# 1_Power_supply.net
KiCad netlist of a schematic drawn in Altium Designer
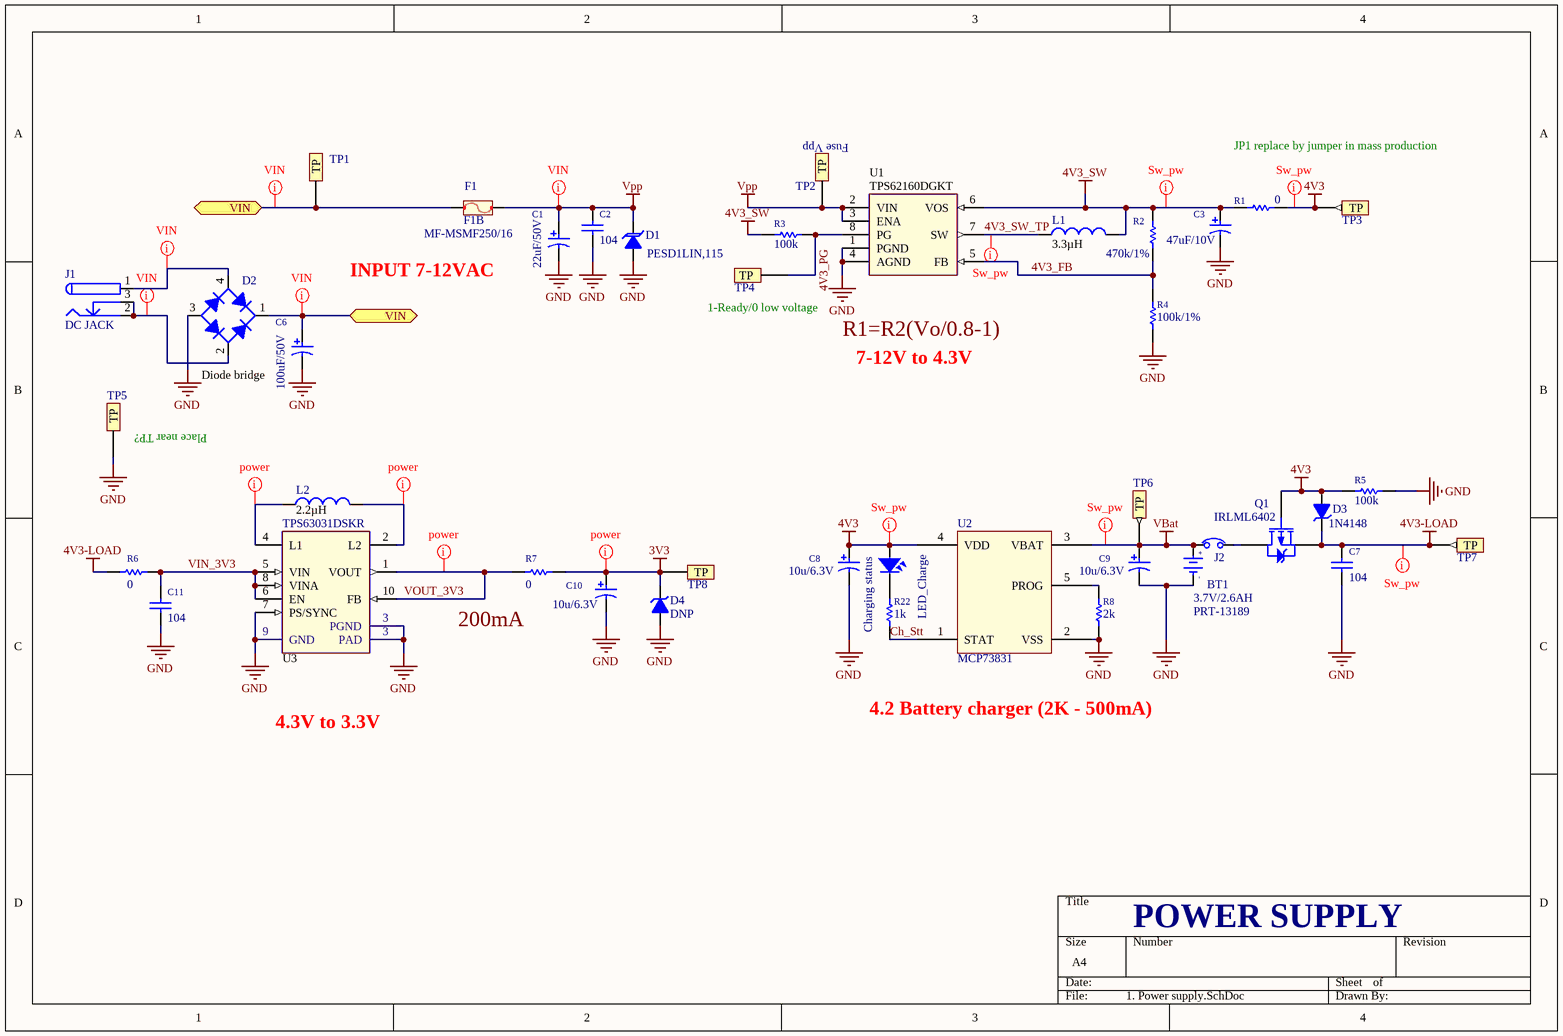
[diagram p0: 1. Power supply.SchDoc]

(export (version "E")
  (design (tool "Eeschema 10.0.6"))
  (components
    (comp (ref "BT1")
      (value "3.7V/2.6AH")
      (footprint "Batterry Cell")
      (description "BATTERY LITHIUM 3.7V 2.6AH")
      (fields
        (field (name "ALTIUM_VALUE") "PRT-13189")
        (field (name "MANUFACTURER") "SparkFun Electronics")
        (field (name "PART") "PRT-13189")
      )
      (libsource (lib "LIB_MISCELLANEOUS") (part "PIN 3V"))
    )
    (comp (ref "C1")
      (value "22uF/50V")
      (footprint "CAP_SMD_6_3MM_N")
      (description "CAP ALUM 22UF 20% 50V SMD")
      (fields (field (name "MANUFACTURER") "Panasonic Electronic Components") (field (name "VOLTAGE") "50V"))
      (libsource (lib "My_Integrated_Library") (part "Cap_Pol"))
    )
    (comp (ref "C2")
      (value "104")
      (footprint "sm-0603-c")
      (description "CAP CER 10000PF 16V 0603")
      (fields (field (name "MANUFACTURER") "Taiyo Yuden") (field (name "PART") "EMK107SD103JA-T"))
      (libsource (lib "My_Integrated_Library") (part "Capacitor"))
    )
    (comp (ref "C3")
      (value "47uF/10V")
      (footprint "Cap SMD Tant - 470u")
      (description "47uF/10V ±10% SMD Tantalum Capacitor")
      (fields (field (name "MANUFACTURER") "AVX") (field (name "VOLTAGE") "10V"))
      (libsource (lib "My_Integrated_Library") (part "Cap_Pol"))
    )
    (comp (ref "C6")
      (value "100uF/50V")
      (footprint "CAP SMD ALUMINUM G.CAOVANHUONG")
      (description "CAP ALUM 22UF 20% 50V SMD")
      (fields (field (name "MANUFACTURER") "Panasonic Electronic Components") (field (name "VOLTAGE") "50V"))
      (libsource (lib "My_Integrated_Library") (part "Cap_Pol"))
    )
    (comp (ref "C7")
      (value "104")
      (footprint "sm-0603-c")
      (description "CAP CER 10000PF 16V 0603")
      (fields (field (name "MANUFACTURER") "Taiyo Yuden") (field (name "PART") "EMK107SD103JA-T"))
      (libsource (lib "My_Integrated_Library") (part "Capacitor"))
    )
    (comp (ref "C8")
      (value "10u/6.3V")
      (footprint "Cap SMD Tant 10u")
      (description "CAP CER 10UF 6.3V X5R 1206")
      (fields (field (name "MANUFACTURER") "Samsung Electro-Mechanics") (field (name "VOLTAGE") "6.3V"))
      (libsource (lib "My_Integrated_Library") (part "Cap_Pol"))
    )
    (comp (ref "C9")
      (value "10u/6.3V")
      (footprint "Cap SMD Tant 10u")
      (description "CAP CER 10UF 6.3V X5R 1206")
      (fields (field (name "MANUFACTURER") "Samsung Electro-Mechanics") (field (name "VOLTAGE") "6.3V"))
      (libsource (lib "My_Integrated_Library") (part "Cap_Pol"))
    )
    (comp (ref "C10")
      (value "10u/6.3V")
      (footprint "Cap SMD Tant 10u")
      (description "CAP CER 10UF 6.3V X5R 1206")
      (fields (field (name "MANUFACTURER") "Samsung Electro-Mechanics") (field (name "VOLTAGE") "6.3V"))
      (libsource (lib "My_Integrated_Library") (part "Cap_Pol"))
    )
    (comp (ref "C11")
      (value "104")
      (footprint "sm-0603-c")
      (description "CAP CER 10000PF 16V 0603")
      (fields (field (name "MANUFACTURER") "Taiyo Yuden") (field (name "PART") "EMK107SD103JA-T"))
      (libsource (lib "My_Integrated_Library") (part "Capacitor"))
    )
    (comp (ref "D1")
      (value "PESD1LIN,115")
      (footprint "DIODE_SMB")
      (description "TVS DIODE 15V/24V 44V/70V SOD323")
      (fields (field (name "MANUFACTURER") "Nexperia USA Inc.") (field (name "POWER") "160W"))
      (libsource (lib "LIB_MISCELLANEOUS") (part "Diode TVS"))
    )
    (comp (ref "D2")
      (value "Diode bridge")
      (footprint "DB-38R")
      (description "Rectifier Bridge")
      (fields (field (name "PART") "Diode_Bridge") (field (name "Comment") "Diode Bridge"))
      (libsource (lib "My_Integrated_Library") (part "Diode_Bridge"))
    )
    (comp (ref "D3")
      (value "1N4148")
      (footprint "DIODE-SOD80")
      (description "Zener Diode")
      (fields (field (name "MANUFACTURER") "Unknow"))
      (libsource (lib "LIB_MISCELLANEOUS") (part "Diode Zener"))
    )
    (comp (ref "D4")
      (value "DNP")
      (footprint "DIODE-SOD80")
      (description "Zener Diode")
      (fields (field (name "MANUFACTURER") "Unknow"))
      (libsource (lib "LIB_MISCELLANEOUS") (part "Diode Zener"))
    )
    (comp (ref "F1")
      (value "F1B")
      (footprint "SMD-PTC")
      (description "2.5A/16V SMD-1812 PTC Resettable Fuses")
      (fields
        (field (name "ALTIUM_VALUE") "MF-MSMF250/16")
        (field (name "MANUFACTURER") "Bourns Inc.")
        (field (name "PART") "MF-MSMF250/16")
      )
      (libsource (lib "LIB_MISCELLANEOUS") (part "Fuse"))
    )
    (comp (ref "J1")
      (value "DC JACK")
      (footprint "DC JACK.CAOVANHUONG")
      (description "Low Voltage Power Supply Connector")
      (fields (field (name "PUBLISHER") "Altium Limited"))
      (libsource (lib "caovanhuong") (part "DC JACK"))
    )
    (comp (ref "J2")
      (value "jumper selector")
      (footprint "CON.HDR1X2")
      (libsource (lib "My_Integrated_Library") (part "jumper selector"))
    )
    (comp (ref "L1")
      (value "3.3µH")
      (footprint "Inductor 2")
      (description "FIXED IND 3.3UH 3.2A 30.2 MOHM")
      (fields (field (name "MANUFACTURER") "Bourns Inc."))
      (libsource (lib "My_Integrated_Library") (part "Inductor"))
    )
    (comp (ref "L2")
      (value "2.2µH")
      (footprint "INDUCTOR 4")
      (description "FIXED IND 2.2UH 2.9A 42 MOHM SMD")
      (fields (field (name "MANUFACTURER") "Taiyo Yuden"))
      (libsource (lib "My_Integrated_Library") (part "Inductor"))
    )
    (comp (ref "LED_Charge")
      (value "Charging status")
      (footprint "LED0603")
      (description "LED Single colour Green and Red")
      (fields (field (name "MANUFACTURER") "Unknow"))
      (libsource (lib "LIB_MISCELLANEOUS") (part "LED"))
    )
    (comp (ref "Q1")
      (value "IRLML6402")
      (footprint "SOT23-3.CAOVANHUONG")
      (description "P-Channel MOSFET, ID =3.7A @ TA = 25°C, VGS @ -4.5V")
      (fields (field (name "PUBLISHER") "Altium Limited"))
      (libsource (lib "caovanhuong") (part "IRLML6402"))
    )
    (comp (ref "R1")
      (value "0")
      (footprint "R2012-0805")
      (description "RES SMD 0 OHM JUMPER 1/10W 0805")
      (fields (field (name "MANUFACTURER") "Panasonic Electronic Components") (field (name "POWER") "1/10W"))
      (libsource (lib "My_Integrated_Library") (part "Resistor"))
    )
    (comp (ref "R2")
      (value "470k/1%")
      (footprint "SM-0603-R")
      (description "RES SMD 470K OHM 1% 1/10W 0603")
      (fields (field (name "MANUFACTURER") "Panasonic Electronic Components") (field (name "PART") "470k"))
      (libsource (lib "My_Integrated_Library") (part "Resistor"))
    )
    (comp (ref "R3")
      (value "100k")
      (footprint "SM-0603-R")
      (description "RES SMD 100K OHM 5% 1/10W 0603")
      (fields (field (name "MANUFACTURER") "Panasonic Electronic Components") (field (name "POWER") "1/10W"))
      (libsource (lib "My_Integrated_Library") (part "Resistor"))
    )
    (comp (ref "R4")
      (value "100k/1%")
      (footprint "SM-0603-R")
      (description "RES SMD 100K OHM 1% 1/10W 0603")
      (fields (field (name "MANUFACTURER") "Panasonic Electronic Components") (field (name "PART") "100k"))
      (libsource (lib "My_Integrated_Library") (part "Resistor"))
    )
    (comp (ref "R5")
      (value "100k")
      (footprint "SM-0603-R")
      (description "RES SMD 100K OHM 5% 1/10W 0603")
      (fields (field (name "MANUFACTURER") "Panasonic Electronic Components") (field (name "POWER") "1/10W"))
      (libsource (lib "My_Integrated_Library") (part "Resistor"))
    )
    (comp (ref "R6")
      (value "0")
      (footprint "R2012-0805")
      (description "RES SMD 0 OHM JUMPER 1/10W 0805")
      (fields (field (name "MANUFACTURER") "Panasonic Electronic Components") (field (name "POWER") "1/10W"))
      (libsource (lib "My_Integrated_Library") (part "Resistor"))
    )
    (comp (ref "R7")
      (value "0")
      (footprint "R2012-0805")
      (description "RES SMD 0 OHM JUMPER 1/10W 0805")
      (fields (field (name "MANUFACTURER") "Panasonic Electronic Components") (field (name "POWER") "1/10W"))
      (libsource (lib "My_Integrated_Library") (part "Resistor"))
    )
    (comp (ref "R8")
      (value "2k")
      (footprint "SM-0603-R")
      (description "RES SMD 100K OHM 5% 1/10W 0603")
      (fields (field (name "MANUFACTURER") "Panasonic Electronic Components") (field (name "PART") "100k"))
      (libsource (lib "My_Integrated_Library") (part "Resistor"))
    )
    (comp (ref "R22")
      (value "1k")
      (footprint "SM-0603-R")
      (description "RES SMD 1K OHM 5% 1/10W 0603")
      (fields (field (name "MANUFACTURER") "Panasonic Electronic Components") (field (name "POWER") "1/10W"))
      (libsource (lib "My_Integrated_Library") (part "Resistor"))
    )
    (comp (ref "TP1")
      (value "Vin")
      (footprint "TP")
      (description "Test Point")
      (libsource (lib "My_Integrated_Library") (part "Test Point"))
    )
    (comp (ref "TP2")
      (value "VIN")
      (footprint "TP")
      (description "Test Point")
      (libsource (lib "My_Integrated_Library") (part "Test Point"))
    )
    (comp (ref "TP3")
      (value "4V3")
      (footprint "TP")
      (description "Test Point")
      (libsource (lib "") (part "Test Point_1"))
    )
    (comp (ref "TP4")
      (value "4V3_PG")
      (footprint "TP")
      (description "Test Point")
      (libsource (lib "") (part "Test Point_3"))
    )
    (comp (ref "TP5")
      (value "GND")
      (footprint "TP")
      (description "Test Point")
      (libsource (lib "My_Integrated_Library") (part "Test Point"))
    )
    (comp (ref "TP6")
      (value "4V3")
      (footprint "TP")
      (description "Test Point")
      (libsource (lib "My_Integrated_Library") (part "Test Point"))
    )
    (comp (ref "TP7")
      (value "4V3")
      (footprint "TP")
      (description "Test Point")
      (libsource (lib "") (part "Test Point_1"))
    )
    (comp (ref "TP8")
      (value "TP")
      (footprint "TP")
      (description "Test Point")
      (libsource (lib "") (part "Test Point_2"))
    )
    (comp (ref "U1")
      (value "TPS62160DGKT")
      (footprint "SSOP8.S-PDSO-G8")
      (description "IC REG BUCK ADJ 1A SYNC 8VSSOP")
      (fields (field (name "MANUFACTURER") "Texas Instruments"))
      (libsource (lib "My_Integrated_Library") (part "TPS62160"))
    )
    (comp (ref "U2")
      (value "MCP73831")
      (footprint "SOT23-5.CAOVANHUONG")
      (description "Miniature Single Cell, Fully Integrated Li-Ion,  Li-Polymer Charge Management ControllerController")
      (fields (field (name "MANUFACTURER") "Microchip"))
      (libsource (lib "caovanhuong") (part "MCP73831"))
    )
    (comp (ref "U3")
      (value "TPS63031DSKR")
      (footprint "WSON10")
      (description "IC REG BUCK BST 3.3V 0.9A 10SON")
      (fields (field (name "MANUFACTURER") "Texas Instruments"))
      (libsource (lib "My_Integrated_Library") (part "TPS63031"))
    )
  )
  (nets
    (net (code "1") (name "/4V3_FB") (class "Default")
      (node (ref "R2") (pin "2") (pinfunction "2_2") (pintype "passive"))
      (node (ref "R4") (pin "1") (pinfunction "1_1") (pintype "passive"))
      (node (ref "U1") (pin "5") (pinfunction "FB_5") (pintype "input"))
    )
    (net (code "2") (name "/4V3_PG") (class "Default")
      (node (ref "R3") (pin "1") (pinfunction "1_1") (pintype "passive"))
      (node (ref "TP4") (pin "1") (pinfunction "TP_1") (pintype "passive"))
      (node (ref "U1") (pin "8") (pinfunction "PG_8") (pintype "open_collector"))
    )
    (net (code "3") (name "/4V3_SW_TP") (class "Default")
      (node (ref "L1") (pin "1") (pinfunction "1_1") (pintype "passive"))
      (node (ref "U1") (pin "7") (pinfunction "SW_7") (pintype "output"))
    )
    (net (code "4") (name "/Ch_Stt") (class "Default")
      (node (ref "R22") (pin "1") (pinfunction "1_1") (pintype "passive"))
      (node (ref "U2") (pin "1") (pinfunction "STAT_1") (pintype "passive"))
    )
    (net (code "5") (name "/VIN") (class "Default")
      (node (ref "C6") (pin "1") (pinfunction "1_1") (pintype "passive"))
      (node (ref "D2") (pin "1") (pinfunction "K_1") (pintype "passive"))
      (node (ref "F1") (pin "1") (pinfunction "1_1") (pintype "passive"))
      (node (ref "TP1") (pin "1") (pinfunction "TP_1") (pintype "passive"))
    )
    (net (code "6") (name "/VIN_3V3") (class "Default")
      (node (ref "C11") (pin "1") (pinfunction "1_1") (pintype "passive"))
      (node (ref "R6") (pin "2") (pinfunction "2_2") (pintype "passive"))
      (node (ref "U3") (pin "5") (pinfunction "VIN_5") (pintype "input"))
      (node (ref "U3") (pin "6") (pinfunction "EN_6") (pintype "power_in"))
      (node (ref "U3") (pin "8") (pinfunction "VINA_8") (pintype "input"))
    )
    (net (code "7") (name "/VOUT_3V3") (class "Default")
      (node (ref "R7") (pin "1") (pinfunction "1_1") (pintype "passive"))
      (node (ref "U3") (pin "1") (pinfunction "VOUT_1") (pintype "output"))
      (node (ref "U3") (pin "10") (pinfunction "FB_10") (pintype "input"))
    )
    (net (code "8") (name "3V3") (class "Default")
      (node (ref "C10") (pin "1") (pinfunction "1_1") (pintype "passive"))
      (node (ref "D4") (pin "2") (pinfunction "K_2") (pintype "passive"))
      (node (ref "R7") (pin "2") (pinfunction "2_2") (pintype "passive"))
      (node (ref "TP8") (pin "1") (pinfunction "TP_1") (pintype "passive"))
    )
    (net (code "9") (name "4V3") (class "Default")
      (node (ref "C8") (pin "1") (pinfunction "1_1") (pintype "passive"))
      (node (ref "D3") (pin "1") (pinfunction "A_1") (pintype "passive"))
      (node (ref "LED_Charge") (pin "1") (pinfunction "1_1") (pintype "passive"))
      (node (ref "Q1") (pin "1") (pinfunction "G_1") (pintype "passive"))
      (node (ref "R1") (pin "2") (pinfunction "2_2") (pintype "passive"))
      (node (ref "R5") (pin "1") (pinfunction "1_1") (pintype "passive"))
      (node (ref "TP3") (pin "1") (pinfunction "TP_1") (pintype "output"))
      (node (ref "U2") (pin "4") (pinfunction "VDD_4") (pintype "passive"))
    )
    (net (code "10") (name "4V3-LOAD") (class "Default")
      (node (ref "C7") (pin "1") (pinfunction "1_1") (pintype "passive"))
      (node (ref "D3") (pin "2") (pinfunction "K_2") (pintype "passive"))
      (node (ref "Q1") (pin "2") (pinfunction "S_2") (pintype "passive"))
      (node (ref "R6") (pin "1") (pinfunction "1_1") (pintype "passive"))
      (node (ref "TP7") (pin "1") (pinfunction "TP_1") (pintype "output"))
    )
    (net (code "11") (name "4V3_SW") (class "Default")
      (node (ref "C3") (pin "1") (pinfunction "1_1") (pintype "passive"))
      (node (ref "L1") (pin "2") (pinfunction "2_2") (pintype "passive"))
      (node (ref "R1") (pin "1") (pinfunction "1_1") (pintype "passive"))
      (node (ref "R2") (pin "1") (pinfunction "1_1") (pintype "passive"))
      (node (ref "R3") (pin "2") (pinfunction "2_2") (pintype "passive"))
      (node (ref "U1") (pin "6") (pinfunction "VOS_6") (pintype "input"))
    )
    (net (code "12") (name "GND") (class "Default")
      (node (ref "BT1") (pin "2") (pinfunction "GND_2") (pintype "passive"))
      (node (ref "C1") (pin "2") (pinfunction "2_2") (pintype "passive"))
      (node (ref "C10") (pin "2") (pinfunction "2_2") (pintype "passive"))
      (node (ref "C11") (pin "2") (pinfunction "2_2") (pintype "passive"))
      (node (ref "C2") (pin "2") (pinfunction "2_2") (pintype "passive"))
      (node (ref "C3") (pin "2") (pinfunction "2_2") (pintype "passive"))
      (node (ref "C6") (pin "2") (pinfunction "2_2") (pintype "passive"))
      (node (ref "C7") (pin "2") (pinfunction "2_2") (pintype "passive"))
      (node (ref "C8") (pin "2") (pinfunction "2_2") (pintype "passive"))
      (node (ref "C9") (pin "2") (pinfunction "2_2") (pintype "passive"))
      (node (ref "D1") (pin "1") (pinfunction "A_1") (pintype "passive"))
      (node (ref "D2") (pin "3") (pinfunction "A_3") (pintype "passive"))
      (node (ref "D4") (pin "1") (pinfunction "A_1") (pintype "passive"))
      (node (ref "R4") (pin "2") (pinfunction "2_2") (pintype "passive"))
      (node (ref "R5") (pin "2") (pinfunction "2_2") (pintype "passive"))
      (node (ref "R8") (pin "2") (pinfunction "2_2") (pintype "passive"))
      (node (ref "TP5") (pin "1") (pinfunction "TP_1") (pintype "passive"))
      (node (ref "U1") (pin "1") (pinfunction "PGND_1") (pintype "power_in"))
      (node (ref "U1") (pin "4") (pinfunction "AGND_4") (pintype "power_in"))
      (node (ref "U2") (pin "2") (pinfunction "VSS_2") (pintype "passive"))
      (node (ref "U3") (pin "3") (pinfunction "PAD_3") (pintype "power_in"))
      (node (ref "U3") (pin "7") (pinfunction "PS/SYNC_7") (pintype "input"))
      (node (ref "U3") (pin "9") (pinfunction "GND_9") (pintype "power_in"))
    )
    (net (code "13") (name "Net-(D2-C-Pad2)") (class "Default")
      (node (ref "D2") (pin "2") (pinfunction "C_2") (pintype "passive"))
      (node (ref "J1") (pin "2") (pinfunction "2_2") (pintype "power_in"))
      (node (ref "J1") (pin "3") (pinfunction "3_3") (pintype "power_in"))
    )
    (net (code "14") (name "Net-(D2-C-Pad4)") (class "Default")
      (node (ref "D2") (pin "4") (pinfunction "C_4") (pintype "passive"))
      (node (ref "J1") (pin "1") (pinfunction "1_1") (pintype "power_in"))
    )
    (net (code "15") (name "Net-(LED_Charge-Pad2)") (class "Default")
      (node (ref "LED_Charge") (pin "2") (pinfunction "2_2") (pintype "passive"))
      (node (ref "R22") (pin "2") (pinfunction "2_2") (pintype "passive"))
    )
    (net (code "16") (name "Net-(Q1-D)") (class "Default")
      (node (ref "J2") (pin "2") (pinfunction "2_2") (pintype "passive"))
      (node (ref "Q1") (pin "3") (pinfunction "D_3") (pintype "passive"))
    )
    (net (code "17") (name "Net-(U2-PROG)") (class "Default")
      (node (ref "R8") (pin "1") (pinfunction "1_1") (pintype "passive"))
      (node (ref "U2") (pin "5") (pinfunction "PROG_5") (pintype "passive"))
    )
    (net (code "18") (name "Net-(U3-L1)") (class "Default")
      (node (ref "L2") (pin "1") (pinfunction "1_1") (pintype "passive"))
      (node (ref "U3") (pin "4") (pinfunction "L1_4") (pintype "power_in"))
    )
    (net (code "19") (name "Net-(U3-L2)") (class "Default")
      (node (ref "L2") (pin "2") (pinfunction "2_2") (pintype "passive"))
      (node (ref "U3") (pin "2") (pinfunction "L2_2") (pintype "power_in"))
    )
    (net (code "20") (name "VBat") (class "Default")
      (node (ref "BT1") (pin "1") (pinfunction "+3V_1") (pintype "passive"))
      (node (ref "C9") (pin "1") (pinfunction "1_1") (pintype "passive"))
      (node (ref "J2") (pin "1") (pinfunction "1_1") (pintype "passive"))
      (node (ref "TP6") (pin "1") (pinfunction "TP_1") (pintype "passive"))
      (node (ref "U2") (pin "3") (pinfunction "VBAT_3") (pintype "passive"))
    )
    (net (code "21") (name "Vpp") (class "Default")
      (node (ref "C1") (pin "1") (pinfunction "1_1") (pintype "passive"))
      (node (ref "C2") (pin "1") (pinfunction "1_1") (pintype "passive"))
      (node (ref "D1") (pin "2") (pinfunction "K_2") (pintype "passive"))
      (node (ref "F1") (pin "2") (pinfunction "2_2") (pintype "passive"))
      (node (ref "TP2") (pin "1") (pinfunction "TP_1") (pintype "passive"))
      (node (ref "U1") (pin "2") (pinfunction "VIN_2") (pintype "power_in"))
      (node (ref "U1") (pin "3") (pinfunction "ENA_3") (pintype "power_in"))
    )
  )
)
